# V3_0.net
KiCad netlist of a schematic drawn in EasyEDA Pro
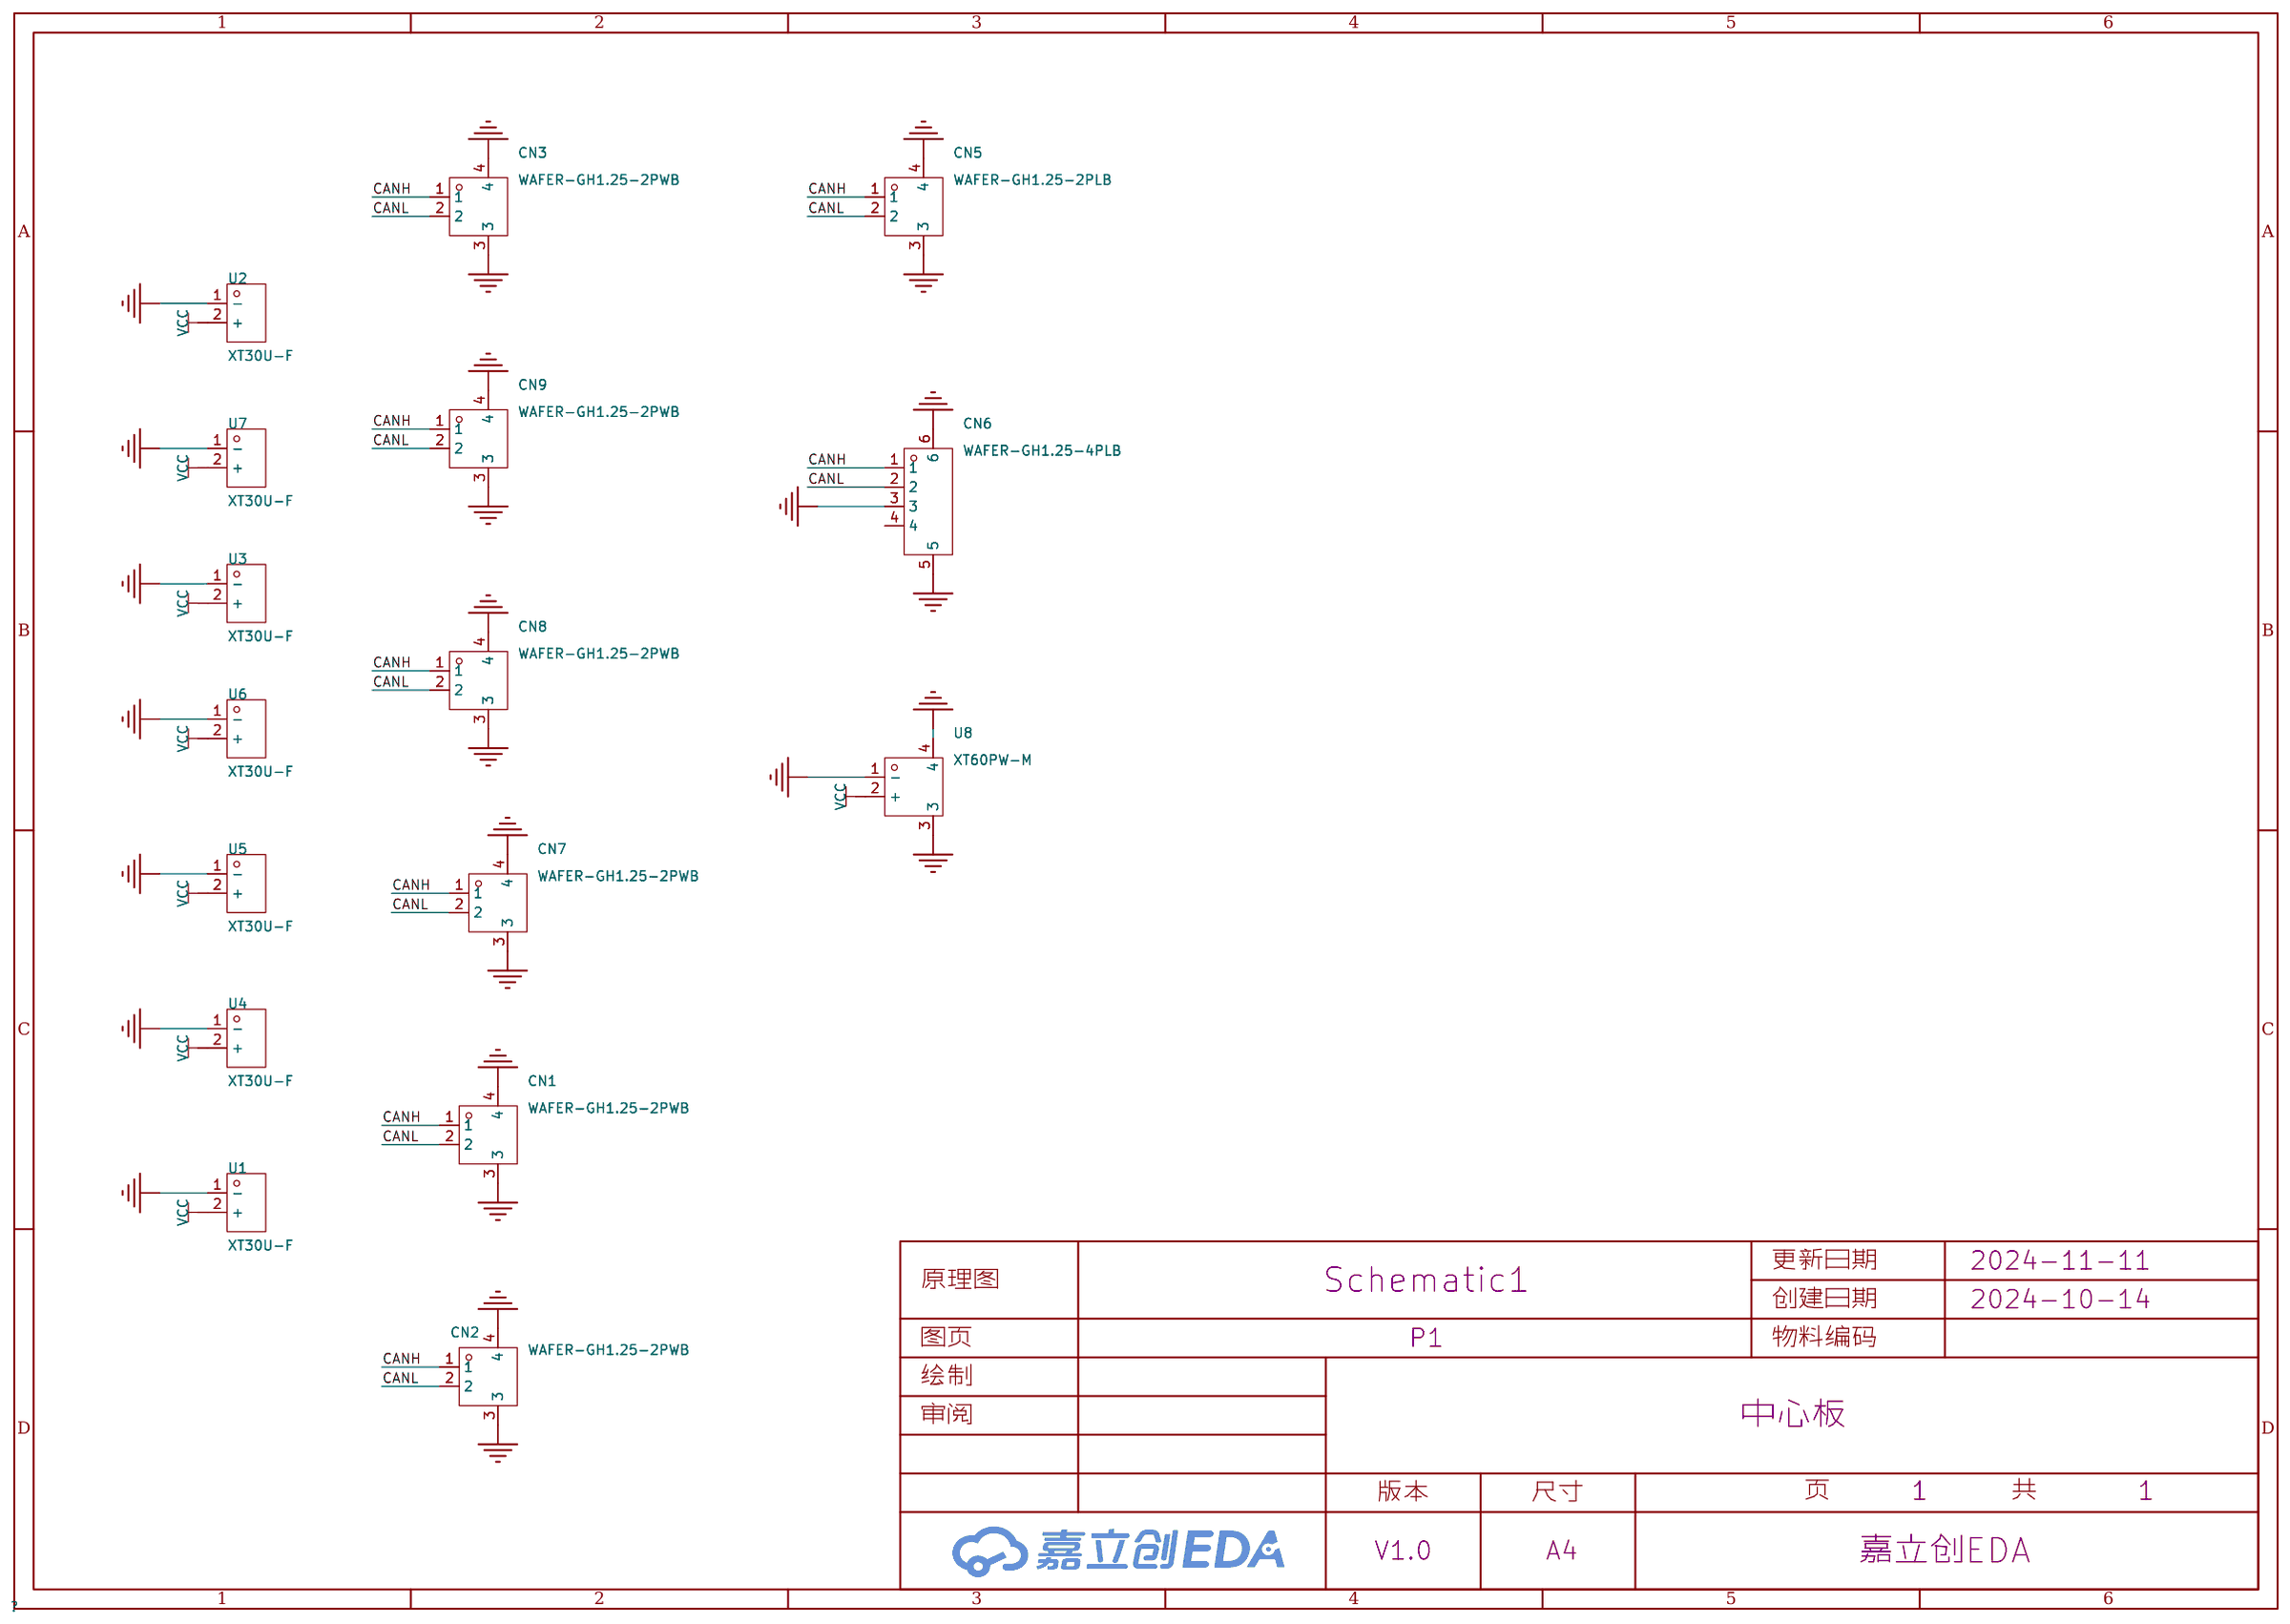
[diagram p0: schematic sheet]

(export (version "E")
  (design (tool "Eeschema 10.0.6"))
  (components
    (comp (ref "CN1")
      (value "WAFER-GH1.25-2PWB")
      (footprint "easyedapro:CONN-TH_2P-P1.25_XUNPU_WAFER-GH1.25-2PWB")
      (description "插针结构:1x2P;间距:1.25mm;安装方式:卧贴;参考系列:GH;总PIN数:2P;排数:1;每排PIN数:2;额定电流:1A;工作温度范围:-25°C~+85°C;")
      (fields (field (name "Manufacturer") "XUNPU(讯普)"))
      (libsource (lib "easyedapro") (part "WAFER-GH1.25-2PWB"))
    )
    (comp (ref "CN2")
      (value "WAFER-GH1.25-2PWB")
      (footprint "easyedapro:CONN-TH_2P-P1.25_XUNPU_WAFER-GH1.25-2PWB")
      (description "插针结构:1x2P;间距:1.25mm;安装方式:卧贴;参考系列:GH;总PIN数:2P;排数:1;每排PIN数:2;额定电流:1A;工作温度范围:-25°C~+85°C;")
      (fields (field (name "Manufacturer") "XUNPU(讯普)"))
      (libsource (lib "easyedapro") (part "WAFER-GH1.25-2PWB"))
    )
    (comp (ref "CN3")
      (value "WAFER-GH1.25-2PWB")
      (footprint "easyedapro:CONN-TH_2P-P1.25_XUNPU_WAFER-GH1.25-2PWB")
      (description "插针结构:1x2P;间距:1.25mm;安装方式:卧贴;参考系列:GH;总PIN数:2P;排数:1;每排PIN数:2;额定电流:1A;工作温度范围:-25°C~+85°C;")
      (fields (field (name "Manufacturer") "XUNPU(讯普)"))
      (libsource (lib "easyedapro") (part "WAFER-GH1.25-2PWB"))
    )
    (comp (ref "CN5")
      (value "WAFER-GH1.25-2PLB")
      (footprint "easyedapro:CONN-TH_2P-P1.25_XUNPU_WAFER-GH1.25-2PLB")
      (description "插针结构:1x2P;间距:1.25mm;安装方式:立贴;参考系列:GH;总PIN数:2P;排数:1;每排PIN数:2;额定电流:1A;工作温度范围:-25°C~+85°C;")
      (fields (field (name "Manufacturer") "XUNPU(讯普)"))
      (libsource (lib "easyedapro") (part "WAFER-GH1.25-2PLB"))
    )
    (comp (ref "CN6")
      (value "WAFER-GH1.25-4PLB")
      (footprint "easyedapro:CONN-SMD_4P-P1.25_XUNPU_WAFER-GH1.25-4PLB")
      (description "插针结构:1x4P;间距:1.25mm;安装方式:立贴;参考系列:GH;总PIN数:4P;排数:1;每排PIN数:4;额定电流:1A;工作温度范围:-25°C~+85°C;")
      (fields (field (name "Manufacturer") "XUNPU(讯普)"))
      (libsource (lib "easyedapro") (part "WAFER-GH1.25-4PLB"))
    )
    (comp (ref "CN7")
      (value "WAFER-GH1.25-2PWB")
      (footprint "easyedapro:CONN-TH_2P-P1.25_XUNPU_WAFER-GH1.25-2PWB")
      (description "插针结构:1x2P;间距:1.25mm;安装方式:卧贴;参考系列:GH;总PIN数:2P;排数:1;每排PIN数:2;额定电流:1A;工作温度范围:-25°C~+85°C;")
      (fields (field (name "Manufacturer") "XUNPU(讯普)"))
      (libsource (lib "easyedapro") (part "WAFER-GH1.25-2PWB"))
    )
    (comp (ref "CN8")
      (value "WAFER-GH1.25-2PWB")
      (footprint "easyedapro:CONN-TH_2P-P1.25_XUNPU_WAFER-GH1.25-2PWB")
      (description "插针结构:1x2P;间距:1.25mm;安装方式:卧贴;参考系列:GH;总PIN数:2P;排数:1;每排PIN数:2;额定电流:1A;工作温度范围:-25°C~+85°C;")
      (fields (field (name "Manufacturer") "XUNPU(讯普)"))
      (libsource (lib "easyedapro") (part "WAFER-GH1.25-2PWB"))
    )
    (comp (ref "CN9")
      (value "WAFER-GH1.25-2PWB")
      (footprint "easyedapro:CONN-TH_2P-P1.25_XUNPU_WAFER-GH1.25-2PWB")
      (description "插针结构:1x2P;间距:1.25mm;安装方式:卧贴;参考系列:GH;总PIN数:2P;排数:1;每排PIN数:2;额定电流:1A;工作温度范围:-25°C~+85°C;")
      (fields (field (name "Manufacturer") "XUNPU(讯普)"))
      (libsource (lib "easyedapro") (part "WAFER-GH1.25-2PWB"))
    )
    (comp (ref "U1")
      (value "XT30U-F")
      (footprint "easyedapro:CONN-TH_XT30U-F")
      (description "类别:-;类型1:-;")
      (fields (field (name "Manufacturer") "AMASS(艾迈斯)"))
      (libsource (lib "easyedapro") (part "XT30U-F"))
    )
    (comp (ref "U2")
      (value "XT30U-F")
      (footprint "easyedapro:CONN-TH_XT30U-F")
      (description "类别:-;类型1:-;")
      (fields (field (name "Manufacturer") "AMASS(艾迈斯)"))
      (libsource (lib "easyedapro") (part "XT30U-F"))
    )
    (comp (ref "U3")
      (value "XT30U-F")
      (footprint "easyedapro:CONN-TH_XT30U-F")
      (description "类别:-;类型1:-;")
      (fields (field (name "Manufacturer") "AMASS(艾迈斯)"))
      (libsource (lib "easyedapro") (part "XT30U-F"))
    )
    (comp (ref "U4")
      (value "XT30U-F")
      (footprint "easyedapro:CONN-TH_XT30U-F")
      (description "类别:-;类型1:-;")
      (fields (field (name "Manufacturer") "AMASS(艾迈斯)"))
      (libsource (lib "easyedapro") (part "XT30U-F"))
    )
    (comp (ref "U5")
      (value "XT30U-F")
      (footprint "easyedapro:CONN-TH_XT30U-F")
      (description "类别:-;类型1:-;")
      (fields (field (name "Manufacturer") "AMASS(艾迈斯)"))
      (libsource (lib "easyedapro") (part "XT30U-F"))
    )
    (comp (ref "U6")
      (value "XT30U-F")
      (footprint "easyedapro:CONN-TH_XT30U-F")
      (description "类别:-;类型1:-;")
      (fields (field (name "Manufacturer") "AMASS(艾迈斯)"))
      (libsource (lib "easyedapro") (part "XT30U-F"))
    )
    (comp (ref "U7")
      (value "XT30U-F")
      (footprint "easyedapro:CONN-TH_XT30U-F")
      (description "类别:-;类型1:-;")
      (fields (field (name "Manufacturer") "AMASS(艾迈斯)"))
      (libsource (lib "easyedapro") (part "XT30U-F"))
    )
    (comp (ref "U8")
      (value "XT60PW-M")
      (footprint "easyedapro:CONN-TH_XT60PW-M")
      (description "类别:-;类型1:-;")
      (fields (field (name "Manufacturer") "AMASS(艾迈斯)"))
      (libsource (lib "easyedapro") (part "XT60PW-M"))
    )
  )
  (nets
    (net (code "1") (name "/CANH") (class "Default")
      (node (ref "CN1") (pin "1") (pinfunction "1_1") (pintype "unspecified"))
      (node (ref "CN2") (pin "1") (pinfunction "1_1") (pintype "unspecified"))
      (node (ref "CN3") (pin "1") (pinfunction "1_1") (pintype "unspecified"))
      (node (ref "CN5") (pin "1") (pinfunction "1_1") (pintype "unspecified"))
      (node (ref "CN6") (pin "1") (pinfunction "1_1") (pintype "unspecified"))
      (node (ref "CN7") (pin "1") (pinfunction "1_1") (pintype "unspecified"))
      (node (ref "CN8") (pin "1") (pinfunction "1_1") (pintype "unspecified"))
      (node (ref "CN9") (pin "1") (pinfunction "1_1") (pintype "unspecified"))
    )
    (net (code "2") (name "/CANL") (class "Default")
      (node (ref "CN1") (pin "2") (pinfunction "2_2") (pintype "unspecified"))
      (node (ref "CN2") (pin "2") (pinfunction "2_2") (pintype "unspecified"))
      (node (ref "CN3") (pin "2") (pinfunction "2_2") (pintype "unspecified"))
      (node (ref "CN5") (pin "2") (pinfunction "2_2") (pintype "unspecified"))
      (node (ref "CN6") (pin "2") (pinfunction "2_2") (pintype "unspecified"))
      (node (ref "CN7") (pin "2") (pinfunction "2_2") (pintype "unspecified"))
      (node (ref "CN8") (pin "2") (pinfunction "2_2") (pintype "unspecified"))
      (node (ref "CN9") (pin "2") (pinfunction "2_2") (pintype "unspecified"))
    )
    (net (code "3") (name "GND") (class "Default")
      (node (ref "CN1") (pin "3") (pinfunction "3_3") (pintype "unspecified"))
      (node (ref "CN1") (pin "4") (pinfunction "4_4") (pintype "unspecified"))
      (node (ref "CN2") (pin "3") (pinfunction "3_3") (pintype "unspecified"))
      (node (ref "CN2") (pin "4") (pinfunction "4_4") (pintype "unspecified"))
      (node (ref "CN3") (pin "3") (pinfunction "3_3") (pintype "unspecified"))
      (node (ref "CN3") (pin "4") (pinfunction "4_4") (pintype "unspecified"))
      (node (ref "CN5") (pin "3") (pinfunction "3_3") (pintype "unspecified"))
      (node (ref "CN5") (pin "4") (pinfunction "4_4") (pintype "unspecified"))
      (node (ref "CN6") (pin "3") (pinfunction "3_3") (pintype "unspecified"))
      (node (ref "CN6") (pin "5") (pinfunction "5_5") (pintype "unspecified"))
      (node (ref "CN6") (pin "6") (pinfunction "6_6") (pintype "unspecified"))
      (node (ref "CN7") (pin "3") (pinfunction "3_3") (pintype "unspecified"))
      (node (ref "CN7") (pin "4") (pinfunction "4_4") (pintype "unspecified"))
      (node (ref "CN8") (pin "3") (pinfunction "3_3") (pintype "unspecified"))
      (node (ref "CN8") (pin "4") (pinfunction "4_4") (pintype "unspecified"))
      (node (ref "CN9") (pin "3") (pinfunction "3_3") (pintype "unspecified"))
      (node (ref "CN9") (pin "4") (pinfunction "4_4") (pintype "unspecified"))
      (node (ref "U1") (pin "1") (pinfunction "-_1") (pintype "unspecified"))
      (node (ref "U2") (pin "1") (pinfunction "-_1") (pintype "unspecified"))
      (node (ref "U3") (pin "1") (pinfunction "-_1") (pintype "unspecified"))
      (node (ref "U4") (pin "1") (pinfunction "-_1") (pintype "unspecified"))
      (node (ref "U5") (pin "1") (pinfunction "-_1") (pintype "unspecified"))
      (node (ref "U6") (pin "1") (pinfunction "-_1") (pintype "unspecified"))
      (node (ref "U7") (pin "1") (pinfunction "-_1") (pintype "unspecified"))
      (node (ref "U8") (pin "1") (pinfunction "-_1") (pintype "unspecified"))
      (node (ref "U8") (pin "3") (pinfunction "3_3") (pintype "unspecified"))
      (node (ref "U8") (pin "4") (pinfunction "4_4") (pintype "unspecified"))
    )
    (net (code "4") (name "VCC") (class "Default")
      (node (ref "U1") (pin "2") (pinfunction "+_2") (pintype "unspecified"))
      (node (ref "U2") (pin "2") (pinfunction "+_2") (pintype "unspecified"))
      (node (ref "U3") (pin "2") (pinfunction "+_2") (pintype "unspecified"))
      (node (ref "U4") (pin "2") (pinfunction "+_2") (pintype "unspecified"))
      (node (ref "U5") (pin "2") (pinfunction "+_2") (pintype "unspecified"))
      (node (ref "U6") (pin "2") (pinfunction "+_2") (pintype "unspecified"))
      (node (ref "U7") (pin "2") (pinfunction "+_2") (pintype "unspecified"))
      (node (ref "U8") (pin "2") (pinfunction "+_2") (pintype "unspecified"))
    )
    (net (code "5") (name "unconnected-(CN6-Pad4)") (class "Default")
      (node (ref "CN6") (pin "4") (pinfunction "4_4") (pintype "unspecified"))
    )
  )
)
